# stars.net
KiCad netlist of a schematic drawn in EasyEDA
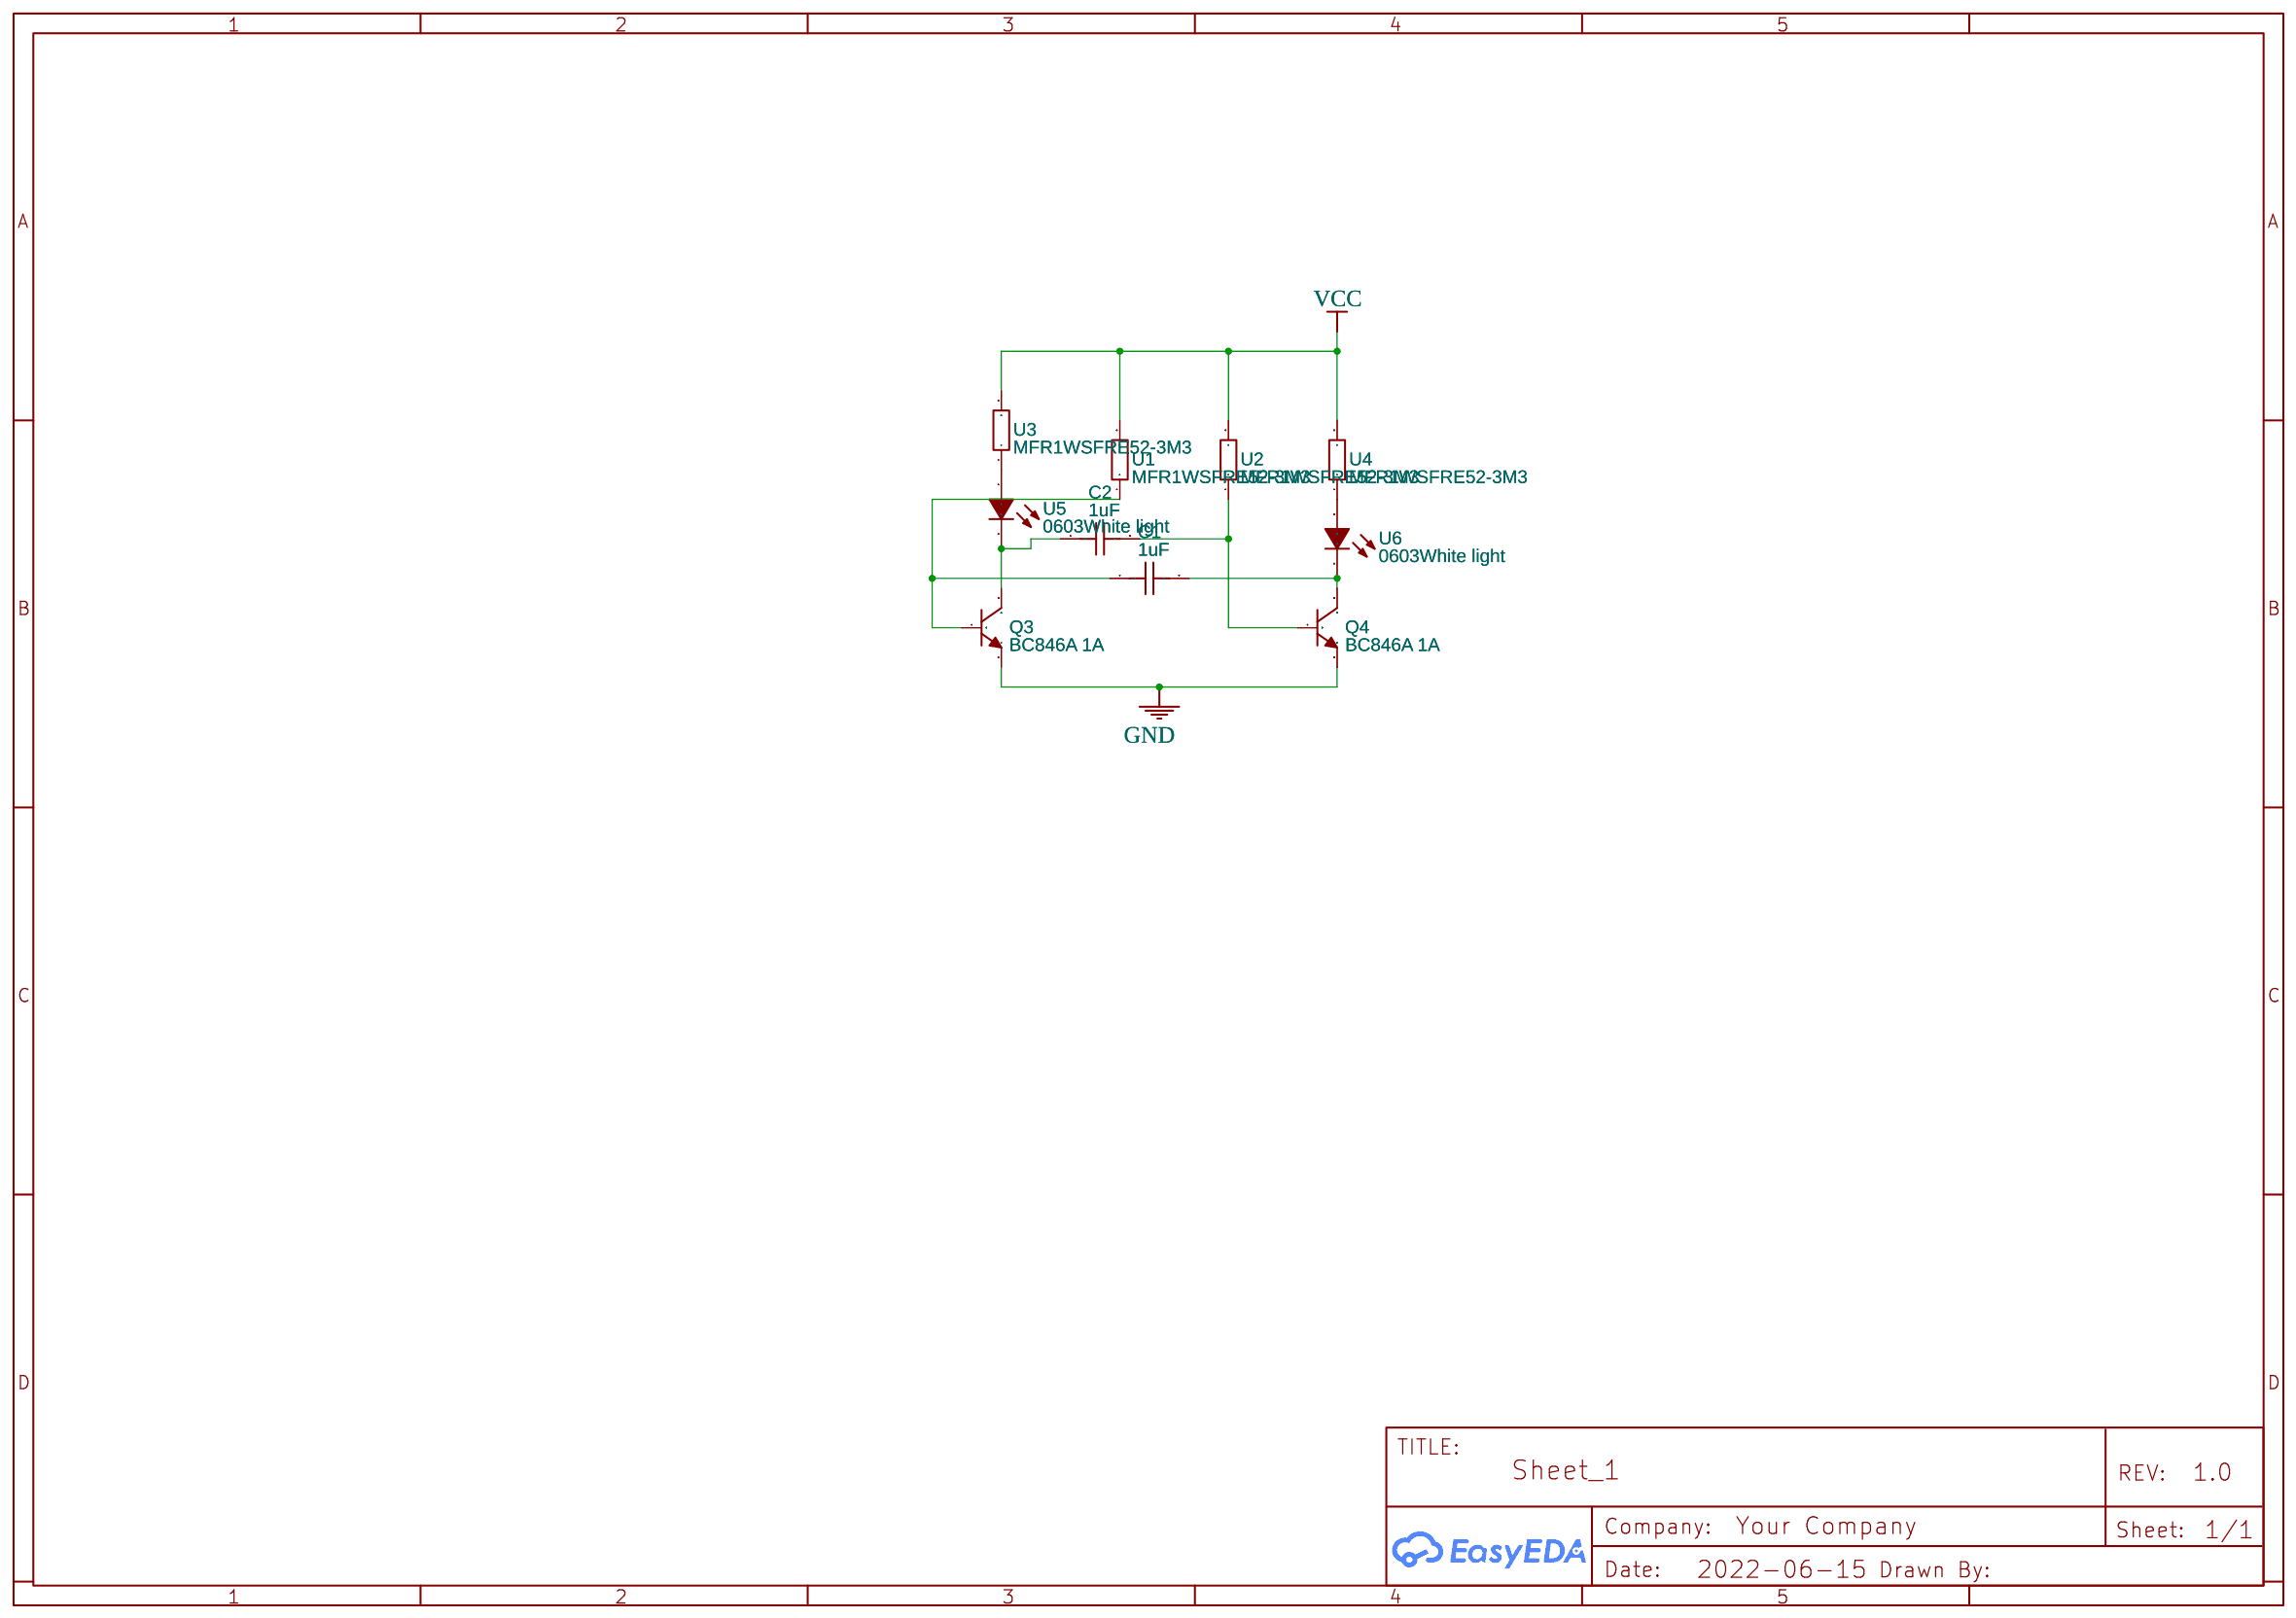
[diagram p0: schematic sheet]

(export (version "E")
  (design (tool "Eeschema 10.0.6"))
  (components
    (comp (ref "C1")
      (value "1uF")
      (fields
        (field (name "BOM_Manufacturer Part") "FK26X7R1H105KRE06")
        (field (name "BOM_Supplier Part") "C2839237")
      )
      (libsource (lib "") (part "FK26X7R1H105KRE06"))
    )
    (comp (ref "C2")
      (value "1uF")
      (fields
        (field (name "BOM_Manufacturer Part") "FK26X7R1H105KRE06")
        (field (name "BOM_Supplier Part") "C2839237")
      )
      (libsource (lib "") (part "FK26X7R1H105KRE06"))
    )
    (comp (ref "Q3")
      (value "BC846A 1A")
      (fields (field (name "BOM_Supplier Part") "C2919760"))
      (libsource (lib "") (part "BC846A 1A"))
    )
    (comp (ref "Q4")
      (value "BC846A 1A")
      (fields (field (name "BOM_Supplier Part") "C2919760"))
      (libsource (lib "") (part "BC846A 1A"))
    )
    (comp (ref "U1")
      (value "MFR1WSFRE52-3M3")
      (fields (field (name "BOM_Supplier Part") "C1760327"))
      (libsource (lib "") (part "MFR1WSFRE52-3M3"))
    )
    (comp (ref "U2")
      (value "MFR1WSFRE52-3M3")
      (fields (field (name "BOM_Supplier Part") "C1760327"))
      (libsource (lib "") (part "MFR1WSFRE52-3M3"))
    )
    (comp (ref "U3")
      (value "MFR1WSFRE52-3M3")
      (fields (field (name "BOM_Supplier Part") "C1760327"))
      (libsource (lib "") (part "MFR1WSFRE52-3M3"))
    )
    (comp (ref "U4")
      (value "MFR1WSFRE52-3M3")
      (fields (field (name "BOM_Supplier Part") "C1760327"))
      (libsource (lib "") (part "MFR1WSFRE52-3M3"))
    )
    (comp (ref "U5")
      (value "0603White light")
      (fields (field (name "BOM_Supplier Part") "C113679"))
      (libsource (lib "") (part "0603White light"))
    )
    (comp (ref "U6")
      (value "0603White light")
      (fields (field (name "BOM_Supplier Part") "C113679"))
      (libsource (lib "") (part "0603White light"))
    )
  )
  (nets
    (net (code "1") (name "GND") (class "Default")
      (node (ref "Q3") (pin "2") (pinfunction "E_2") (pintype "unspecified"))
      (node (ref "Q4") (pin "2") (pinfunction "E_2") (pintype "unspecified"))
    )
    (net (code "2") (name "Net-(Q3-B)") (class "Default")
      (node (ref "C1") (pin "1") (pinfunction "1_1") (pintype "unspecified"))
      (node (ref "Q3") (pin "1") (pinfunction "B_1") (pintype "unspecified"))
      (node (ref "U1") (pin "1") (pinfunction "1_1") (pintype "unspecified"))
    )
    (net (code "3") (name "Net-(Q3-C)") (class "Default")
      (node (ref "C2") (pin "1") (pinfunction "1_1") (pintype "unspecified"))
      (node (ref "Q3") (pin "3") (pinfunction "C_3") (pintype "unspecified"))
      (node (ref "U5") (pin "2") (pinfunction "K_2") (pintype "input"))
    )
    (net (code "4") (name "Net-(Q4-B)") (class "Default")
      (node (ref "C2") (pin "2") (pinfunction "2_2") (pintype "unspecified"))
      (node (ref "Q4") (pin "1") (pinfunction "B_1") (pintype "unspecified"))
      (node (ref "U2") (pin "1") (pinfunction "1_1") (pintype "unspecified"))
    )
    (net (code "5") (name "Net-(Q4-C)") (class "Default")
      (node (ref "C1") (pin "2") (pinfunction "2_2") (pintype "unspecified"))
      (node (ref "Q4") (pin "3") (pinfunction "C_3") (pintype "unspecified"))
      (node (ref "U6") (pin "2") (pinfunction "K_2") (pintype "input"))
    )
    (net (code "6") (name "Net-(U5-A)") (class "Default")
      (node (ref "U3") (pin "1") (pinfunction "1_1") (pintype "unspecified"))
      (node (ref "U5") (pin "1") (pinfunction "A_1") (pintype "input"))
    )
    (net (code "7") (name "Net-(U6-A)") (class "Default")
      (node (ref "U4") (pin "1") (pinfunction "1_1") (pintype "unspecified"))
      (node (ref "U6") (pin "1") (pinfunction "A_1") (pintype "input"))
    )
    (net (code "8") (name "VCC") (class "Default")
      (node (ref "U1") (pin "2") (pinfunction "2_2") (pintype "unspecified"))
      (node (ref "U2") (pin "2") (pinfunction "2_2") (pintype "unspecified"))
      (node (ref "U3") (pin "2") (pinfunction "2_2") (pintype "unspecified"))
      (node (ref "U4") (pin "2") (pinfunction "2_2") (pintype "unspecified"))
    )
  )
)
